# circuit.net
KiCad netlist of a schematic drawn in EAGLE
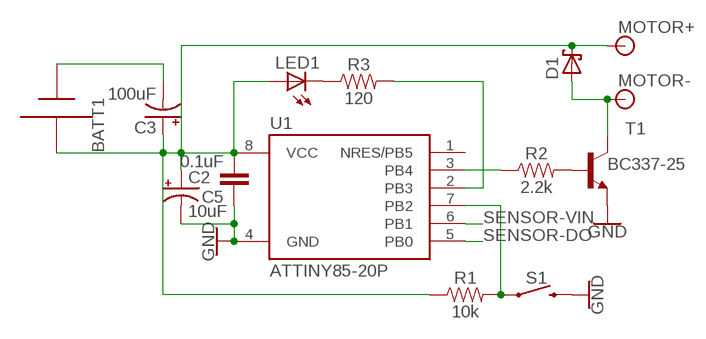
[diagram p0: schematic, sheet 1]

(export (version "E")
  (design (tool "Eeschema 10.0.6"))
  (components
    (comp (ref "BATT1")
      (value "AAA")
      (footprint "eagle-import:12BH412")
      (libsource (lib "eagle-import") (part "AAA"))
    )
    (comp (ref "C2")
      (value "10uF")
      (footprint "eagle-import:0603-POLAR")
      (libsource (lib "eagle-import") (part "10UF-POLAR-0603-6.3V-20%(TANT)"))
    )
    (comp (ref "C3")
      (value "100uF")
      (footprint "eagle-import:0603-POLAR")
      (libsource (lib "eagle-import") (part "10UF-POLAR-0603-6.3V-20%(TANT)"))
    )
    (comp (ref "C5")
      (value "0.1uF")
      (footprint "eagle-import:CAP-PTH-SMALL-KIT")
      (libsource (lib "eagle-import") (part "0.1UF-KIT-EZ-50V-20%"))
    )
    (comp (ref "D1")
      (value "SCHOTTKY-DIODEAG")
      (footprint "eagle-import:AG")
      (libsource (lib "eagle-import") (part "SCHOTTKY-DIODEAG"))
    )
    (comp (ref "LED1")
      (value "LED3MM")
      (footprint "eagle-import:LED3MM")
      (libsource (lib "eagle-import") (part "LED3MM"))
    )
    (comp (ref "MOTOR+")
      (value "BANANA_CONN")
      (footprint "eagle-import:BANANA_CONN")
      (libsource (lib "eagle-import") (part "BANANA_CONN"))
    )
    (comp (ref "MOTOR-")
      (value "BANANA_CONN")
      (footprint "eagle-import:BANANA_CONN")
      (libsource (lib "eagle-import") (part "BANANA_CONN"))
    )
    (comp (ref "R1")
      (value "10k")
      (footprint "eagle-import:AXIAL-0.3")
      (libsource (lib "eagle-import") (part "100OHM-HORIZ-1/4W-1%"))
    )
    (comp (ref "R2")
      (value "2.2k")
      (footprint "eagle-import:0603")
      (libsource (lib "eagle-import") (part "2.2KOHM-0603-1/10W-1%"))
    )
    (comp (ref "R3")
      (value "120")
      (footprint "eagle-import:AXIAL-0.3")
      (libsource (lib "eagle-import") (part "100OHM-HORIZ-1/4W-1%"))
    )
    (comp (ref "S1")
      (value "MOMENTARY-SWITCH-SPST-PTH-6.0MM")
      (footprint "eagle-import:TACTILE_SWITCH_PTH_6.0MM")
      (libsource (lib "eagle-import") (part "MOMENTARY-SWITCH-SPST-PTH-6.0MM"))
    )
    (comp (ref "T1")
      (value "2N2222")
      (footprint "eagle-import:TO92-EBC-OVAL")
      (fields (field (name "MODEL") "BC337-25"))
      (libsource (lib "eagle-import") (part "2N2222"))
    )
    (comp (ref "U1")
      (value "ATTINY85-20P")
      (footprint "eagle-import:PDIP08_300MIL")
      (libsource (lib "eagle-import") (part "ATTINY85P-20"))
    )
  )
  (nets
    (net (code "1") (name "/SENSOR-DO") (class "Default")
      (node (ref "U1") (pin "5") (pinfunction "PB0_5") (pintype "bidirectional"))
    )
    (net (code "2") (name "/SENSOR-VIN") (class "Default")
      (node (ref "U1") (pin "6") (pinfunction "PB1_6") (pintype "bidirectional"))
    )
    (net (code "3") (name "GND") (class "Default")
      (node (ref "C2") (pin "-") (pinfunction "-_-") (pintype "passive"))
      (node (ref "C5") (pin "1") (pinfunction "1_1") (pintype "passive"))
      (node (ref "S1") (pin "3") (pinfunction "2_3") (pintype "passive"))
      (node (ref "T1") (pin "E") (pinfunction "E_E") (pintype "passive"))
      (node (ref "U1") (pin "4") (pinfunction "GND_4") (pintype "power_in"))
    )
    (net (code "4") (name "Net-(BATT1-Pad+)") (class "Default")
      (node (ref "BATT1") (pin "+") (pinfunction "+_+") (pintype "bidirectional"))
      (node (ref "C3") (pin "-") (pinfunction "-_-") (pintype "passive"))
    )
    (net (code "5") (name "Net-(LED1-C)") (class "Default")
      (node (ref "LED1") (pin "K") (pinfunction "C_K") (pintype "passive"))
      (node (ref "R3") (pin "P$1") (pinfunction "1_P$1") (pintype "passive"))
    )
    (net (code "6") (name "Net-(MOTOR+-1)") (class "Default")
      (node (ref "BATT1") (pin "-") (pinfunction "-_-") (pintype "bidirectional"))
      (node (ref "C2") (pin "+") (pinfunction "+_+") (pintype "passive"))
      (node (ref "C3") (pin "+") (pinfunction "+_+") (pintype "passive"))
      (node (ref "C5") (pin "2") (pinfunction "2_2") (pintype "passive"))
      (node (ref "D1") (pin "C") (pinfunction "C_C") (pintype "passive"))
      (node (ref "LED1") (pin "A") (pinfunction "A_A") (pintype "passive"))
      (node (ref "MOTOR+") (pin "P$1") (pinfunction "1_P$1") (pintype "passive"))
      (node (ref "R1") (pin "P$1") (pinfunction "1_P$1") (pintype "passive"))
      (node (ref "U1") (pin "8") (pinfunction "VCC_8") (pintype "power_in"))
    )
    (net (code "7") (name "Net-(MOTOR--1)") (class "Default")
      (node (ref "D1") (pin "A") (pinfunction "A_A") (pintype "passive"))
      (node (ref "MOTOR-") (pin "P$1") (pinfunction "1_P$1") (pintype "passive"))
      (node (ref "T1") (pin "C") (pinfunction "C_C") (pintype "passive"))
    )
    (net (code "8") (name "Net-(R1-2)") (class "Default")
      (node (ref "R1") (pin "P$2") (pinfunction "2_P$2") (pintype "passive"))
      (node (ref "S1") (pin "1") (pinfunction "1_1") (pintype "passive"))
      (node (ref "U1") (pin "7") (pinfunction "PB2_7") (pintype "bidirectional"))
    )
    (net (code "9") (name "Net-(R2-Pad2)") (class "Default")
      (node (ref "R2") (pin "2") (pinfunction "2_2") (pintype "passive"))
      (node (ref "T1") (pin "B") (pinfunction "B_B") (pintype "passive"))
    )
    (net (code "10") (name "Net-(R3-2)") (class "Default")
      (node (ref "R3") (pin "P$2") (pinfunction "2_P$2") (pintype "passive"))
      (node (ref "U1") (pin "2") (pinfunction "PB3_2") (pintype "bidirectional"))
    )
    (net (code "11") (name "Net-(U1-PB4)") (class "Default")
      (node (ref "R2") (pin "1") (pinfunction "1_1") (pintype "passive"))
      (node (ref "U1") (pin "3") (pinfunction "PB4_3") (pintype "bidirectional"))
    )
    (net (code "12") (name "unconnected-(U1-NRES{slash}PB5-Pad1)") (class "Default")
      (node (ref "U1") (pin "1") (pinfunction "NRES/PB5_1") (pintype "bidirectional"))
    )
  )
)
